# 07_EL_CON.net
KiCad netlist of a schematic drawn in Altium Designer
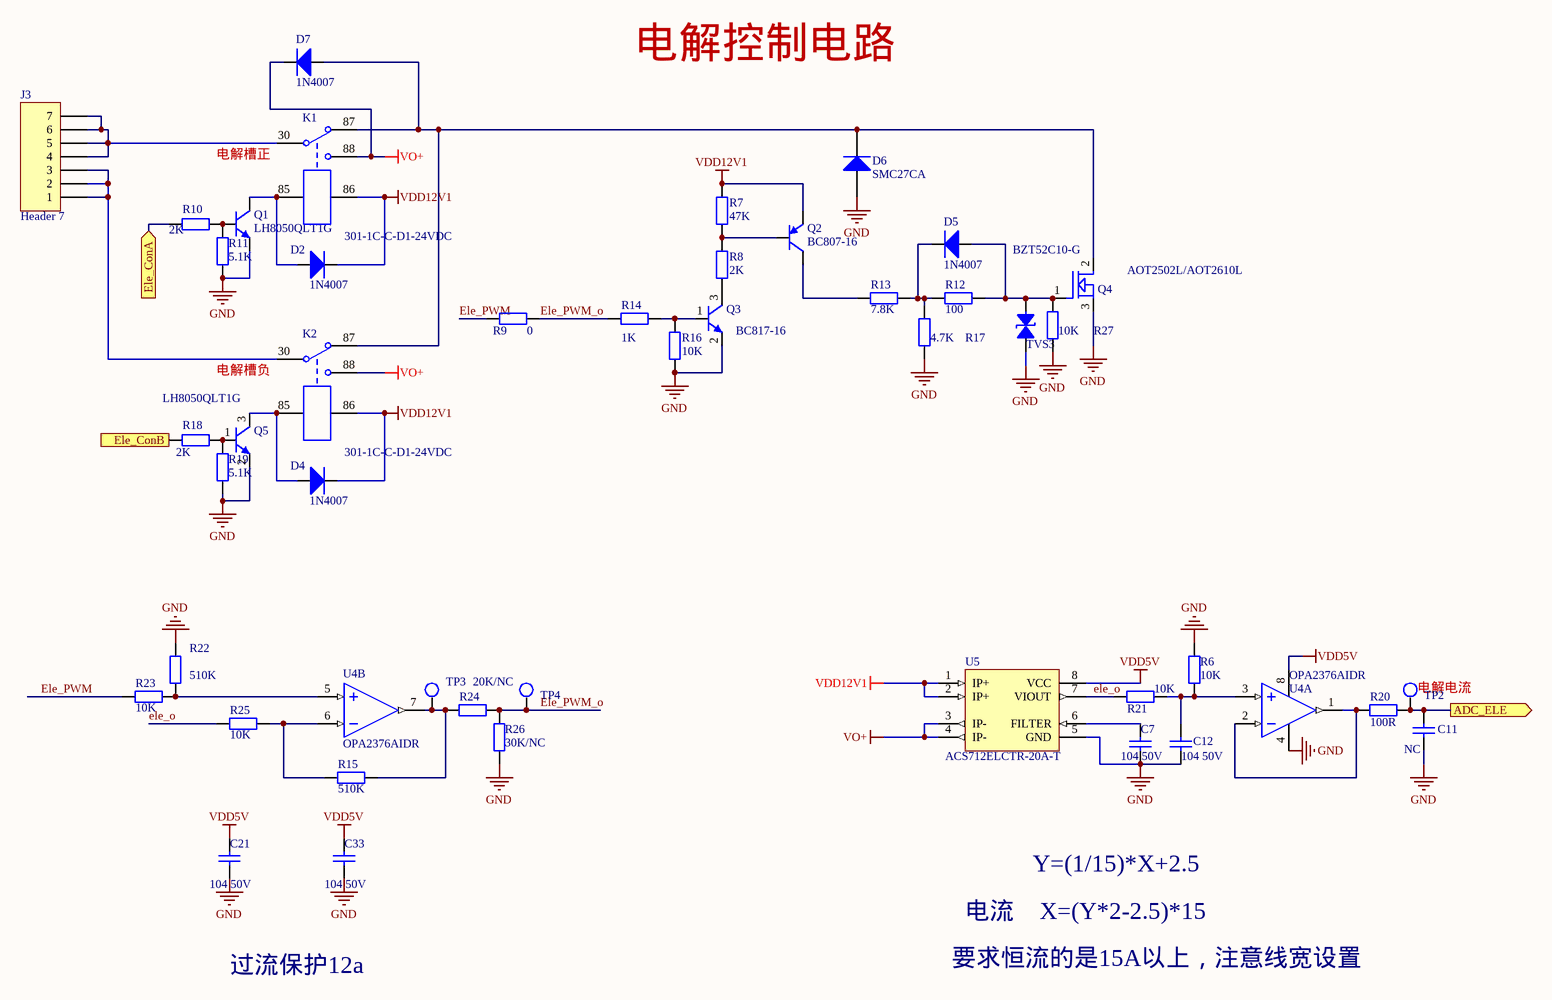
[diagram p0: 07_EL_CON.SchDoc]

(export (version "E")
  (design (tool "Eeschema 10.0.6"))
  (components
    (comp (ref "C7")
      (value "104 50V")
      (footprint "SMD-0603C")
      (description "贴片电容 10%")
      (libsource (lib "XiaoyI") (part "CAP4"))
    )
    (comp (ref "C11")
      (value "NC")
      (footprint "SMD-0603C")
      (description "贴片电容 10%")
      (libsource (lib "XiaoyI") (part "CAP4"))
    )
    (comp (ref "C12")
      (value "104 50V")
      (footprint "SMD-0603C")
      (description "贴片电容 10%")
      (libsource (lib "XiaoyI") (part "CAP4"))
    )
    (comp (ref "C21")
      (value "104 50V")
      (footprint "SMD-0603C")
      (description "贴片电容 20%")
      (libsource (lib "XiaoyI") (part "CAP4"))
    )
    (comp (ref "C33")
      (value "104 50V")
      (footprint "SMD-0603C")
      (description "贴片电容 20%")
      (libsource (lib "XiaoyI") (part "CAP4"))
    )
    (comp (ref "D2")
      (value "1N4007")
      (footprint "DO-214-AC")
      (description "贴片二极管")
      (libsource (lib "XiaoyI") (part "DIODE2"))
    )
    (comp (ref "D4")
      (value "1N4007")
      (footprint "DO-214-AC")
      (description "贴片二极管")
      (libsource (lib "XiaoyI") (part "DIODE2"))
    )
    (comp (ref "D5")
      (value "1N4007")
      (footprint "DO-214-AC")
      (description "贴片二极管")
      (libsource (lib "XiaoyI") (part "DIODE2"))
    )
    (comp (ref "D6")
      (value "SMC27CA")
      (footprint "Pcblib_20110825:SMC")
      (libsource (lib "Sch_library") (part "DIODE"))
    )
    (comp (ref "D7")
      (value "1N4007")
      (footprint "DO-214-AC")
      (description "贴片二极管")
      (libsource (lib "XiaoyI") (part "DIODE2"))
    )
    (comp (ref "J3")
      (value "Header 7")
      (footprint "VH-AW-3.96*7P")
      (description "Header, 7-Pin")
      (fields (field (name "PUBLISHER") "Altium Limited"))
      (libsource (lib "Miscellaneous Connectors") (part "Header 7"))
    )
    (comp (ref "K1")
      (value "301-1C-C-D1-24VDC")
      (footprint "PCB1:301-1C-C-R1-24VDC")
      (description "5V 继电器")
      (libsource (lib "XiaoyI") (part "JDQ1"))
    )
    (comp (ref "K2")
      (value "301-1C-C-D1-24VDC")
      (footprint "PCB1:301-1C-C-R1-24VDC")
      (description "5V 继电器")
      (libsource (lib "XiaoyI") (part "JDQ1"))
    )
    (comp (ref "Q1")
      (value "LH8050QLT1G")
      (footprint "SOT-23")
      (description "三极管")
      (libsource (lib "XiaoyI") (part "NPN-1"))
    )
    (comp (ref "Q2")
      (value "BC807-16")
      (footprint "SOT-23")
      (description "PNP")
      (libsource (lib "XiaoyI") (part "PNP"))
    )
    (comp (ref "Q3")
      (value "BC817-16")
      (footprint "SOT-23")
      (description "三极管")
      (libsource (lib "") (part "NPN-1_1"))
    )
    (comp (ref "Q4")
      (value "AOT2502L/AOT2610L")
      (footprint "Pcblib_20110825:to220")
      (libsource (lib "POWER") (part "SI7860"))
    )
    (comp (ref "Q5")
      (value "LH8050QLT1G")
      (footprint "SOT-23")
      (description "三极管")
      (libsource (lib "") (part "NPN-1_1"))
    )
    (comp (ref "R6")
      (value "10K")
      (footprint "SMD-0603")
      (description "贴片电阻 1%")
      (libsource (lib "") (part "RES0_1"))
    )
    (comp (ref "R7")
      (value "47K")
      (footprint "SMD-0603")
      (description "贴片电阻 5%")
      (libsource (lib "XiaoyI") (part "RES-SOP"))
    )
    (comp (ref "R8")
      (value "2K")
      (footprint "SMD-0603")
      (description "贴片电阻 5%")
      (libsource (lib "XiaoyI") (part "RES-SOP"))
    )
    (comp (ref "R9")
      (value "0")
      (footprint "SMD-0603")
      (description "贴片电阻 5%")
      (libsource (lib "") (part "RES-SOP_1"))
    )
    (comp (ref "R10")
      (value "2K")
      (footprint "SMD-0603")
      (description "贴片电阻 5%")
      (libsource (lib "XiaoyI") (part "RES2"))
    )
    (comp (ref "R11")
      (value "5.1K")
      (footprint "SMD-0603")
      (description "贴片电阻 5%")
      (libsource (lib "") (part "RES2_1"))
    )
    (comp (ref "R12")
      (value "100")
      (footprint "SMD-0603")
      (description "贴片电阻 5%")
      (libsource (lib "") (part "RES-SOP_3"))
    )
    (comp (ref "R13")
      (value "7.8K")
      (footprint "SMD-0603")
      (description "贴片电阻 5%")
      (libsource (lib "") (part "RES-SOP_1"))
    )
    (comp (ref "R14")
      (value "1K")
      (footprint "SMD-0603")
      (description "贴片电阻 5%")
      (libsource (lib "") (part "RES-SOP_1"))
    )
    (comp (ref "R15")
      (value "510K")
      (footprint "SMD-0603")
      (description "贴片电阻 5%")
      (libsource (lib "") (part "RES-SOP_1"))
    )
    (comp (ref "R16")
      (value "10K")
      (footprint "SMD-0603")
      (description "贴片电阻 5%")
      (libsource (lib "XiaoyI") (part "RES-SOP"))
    )
    (comp (ref "R17")
      (value "4.7K")
      (footprint "SMD-0603")
      (description "贴片电阻 5%")
      (libsource (lib "") (part "RES-SOP_2"))
    )
    (comp (ref "R18")
      (value "2K")
      (footprint "SMD-0603")
      (description "贴片电阻 5%")
      (libsource (lib "XiaoyI") (part "RES2"))
    )
    (comp (ref "R19")
      (value "5.1K")
      (footprint "SMD-0603")
      (description "贴片电阻 5%")
      (libsource (lib "") (part "RES2_1"))
    )
    (comp (ref "R20")
      (value "100R")
      (footprint "SMD-0603")
      (description "贴片电阻 5%")
      (libsource (lib "ABB") (part "RES0"))
    )
    (comp (ref "R21")
      (value "10K")
      (footprint "SMD-0603")
      (description "贴片电阻 1%")
      (libsource (lib "ABB") (part "RES0"))
    )
    (comp (ref "R22")
      (value "510K")
      (footprint "SMD-0603")
      (description "贴片电阻 5%")
      (libsource (lib "XiaoyI") (part "RES-SOP"))
    )
    (comp (ref "R23")
      (value "10K")
      (footprint "SMD-0603")
      (description "贴片电阻 5%")
      (libsource (lib "") (part "RES-SOP_1"))
    )
    (comp (ref "R24")
      (value "20K/NC")
      (footprint "SMD-0603")
      (description "贴片电阻 5%")
      (libsource (lib "") (part "RES-SOP_1"))
    )
    (comp (ref "R25")
      (value "10K")
      (footprint "SMD-0603")
      (description "贴片电阻 5%")
      (libsource (lib "") (part "RES-SOP_1"))
    )
    (comp (ref "R26")
      (value "30K/NC")
      (footprint "SMD-0603")
      (description "贴片电阻 5%")
      (libsource (lib "") (part "RES-SOP_2"))
    )
    (comp (ref "R27")
      (value "10K")
      (footprint "SMD-0603")
      (description "贴片电阻 5%")
      (libsource (lib "") (part "RES-SOP_2"))
    )
    (comp (ref "TP2") (value "TPS") (footprint "tpd") (libsource (lib "stm32") (part "TPS")))
    (comp (ref "TP3") (value "TPS") (footprint "tpd") (libsource (lib "stm32") (part "TPS")))
    (comp (ref "TP4") (value "TPS") (footprint "tpd") (libsource (lib "stm32") (part "TPS")))
    (comp (ref "TVS3")
      (value "BZT52C10-G")
      (footprint "SOD-123")
      (description "TVS 10V")
      (libsource (lib "XiaoyI") (part "TVS-1"))
    )
    (comp (ref "U4")
      (value "OPA2376AIDR")
      (footprint "SO-8")
      (description "运算放大器")
      (libsource (lib "XiaoyI") (part "LM358"))
    )
    (comp (ref "U5")
      (value "ACS712ELCTR-20A-T")
      (footprint "SO-8")
      (description "HALL 20A 电流传感器")
      (libsource (lib "XiaoyI") (part "ACS712"))
    )
  )
  (nets
    (net (code "1") (name "/ADC_ELE") (class "Default")
      (node (ref "C11") (pin "2") (pinfunction "2_2") (pintype "passive"))
      (node (ref "R20") (pin "1") (pinfunction "1_1") (pintype "passive"))
      (node (ref "TP2") (pin "1") (pinfunction "1_1") (pintype "passive"))
    )
    (net (code "2") (name "/Ele_ConA") (class "Default")
      (node (ref "R10") (pin "1") (pinfunction "1_1") (pintype "passive"))
    )
    (net (code "3") (name "/Ele_ConB") (class "Default")
      (node (ref "R18") (pin "1") (pinfunction "1_1") (pintype "passive"))
    )
    (net (code "4") (name "/Ele_PWM") (class "Default")
      (node (ref "R23") (pin "2") (pinfunction "2_2") (pintype "passive"))
      (node (ref "R9") (pin "2") (pinfunction "2_2") (pintype "passive"))
    )
    (net (code "5") (name "/Ele_PWM_o") (class "Default")
      (node (ref "R14") (pin "2") (pinfunction "2_2") (pintype "passive"))
      (node (ref "R24") (pin "1") (pinfunction "1_1") (pintype "passive"))
      (node (ref "R26") (pin "1") (pinfunction "1_1") (pintype "passive"))
      (node (ref "R9") (pin "1") (pinfunction "1_1") (pintype "passive"))
      (node (ref "TP4") (pin "1") (pinfunction "1_1") (pintype "passive"))
    )
    (net (code "6") (name "/ele_o") (class "Default")
      (node (ref "R21") (pin "2") (pinfunction "2_2") (pintype "passive"))
      (node (ref "R25") (pin "2") (pinfunction "2_2") (pintype "passive"))
      (node (ref "U5") (pin "7") (pinfunction "VIOUT_7") (pintype "output"))
    )
    (net (code "7") (name "GND") (class "Default")
      (node (ref "C11") (pin "1") (pinfunction "1_1") (pintype "passive"))
      (node (ref "C12") (pin "2") (pinfunction "2_2") (pintype "passive"))
      (node (ref "C21") (pin "1") (pinfunction "1_1") (pintype "passive"))
      (node (ref "C33") (pin "1") (pinfunction "1_1") (pintype "passive"))
      (node (ref "C7") (pin "2") (pinfunction "2_2") (pintype "passive"))
      (node (ref "D6") (pin "1") (pinfunction "A_1") (pintype "passive"))
      (node (ref "Q1") (pin "2") (pinfunction "E_2") (pintype "passive"))
      (node (ref "Q3") (pin "2") (pinfunction "E_2") (pintype "passive"))
      (node (ref "Q4") (pin "3") (pinfunction "S_3") (pintype "passive"))
      (node (ref "Q5") (pin "2") (pinfunction "E_2") (pintype "passive"))
      (node (ref "R11") (pin "1") (pinfunction "1_1") (pintype "passive"))
      (node (ref "R16") (pin "1") (pinfunction "1_1") (pintype "passive"))
      (node (ref "R17") (pin "2") (pinfunction "2_2") (pintype "passive"))
      (node (ref "R19") (pin "1") (pinfunction "1_1") (pintype "passive"))
      (node (ref "R22") (pin "2") (pinfunction "2_2") (pintype "passive"))
      (node (ref "R26") (pin "2") (pinfunction "2_2") (pintype "passive"))
      (node (ref "R27") (pin "2") (pinfunction "2_2") (pintype "passive"))
      (node (ref "R6") (pin "1") (pinfunction "1_1") (pintype "passive"))
      (node (ref "TVS3") (pin "1") (pinfunction "A_1") (pintype "passive"))
      (node (ref "U4") (pin "4") (pinfunction "V-_4") (pintype "power_in"))
      (node (ref "U5") (pin "5") (pinfunction "GND_5") (pintype "power_in"))
    )
    (net (code "8") (name "Net-(D2-A)") (class "Default")
      (node (ref "D2") (pin "1") (pinfunction "A_1") (pintype "passive"))
      (node (ref "K1") (pin "85") (pinfunction "4_85") (pintype "passive"))
      (node (ref "Q1") (pin "3") (pinfunction "C_3") (pintype "passive"))
    )
    (net (code "9") (name "Net-(D4-A)") (class "Default")
      (node (ref "D4") (pin "1") (pinfunction "A_1") (pintype "passive"))
      (node (ref "K2") (pin "85") (pinfunction "4_85") (pintype "passive"))
      (node (ref "Q5") (pin "3") (pinfunction "C_3") (pintype "passive"))
    )
    (net (code "10") (name "Net-(D5-A)") (class "Default")
      (node (ref "D5") (pin "1") (pinfunction "A_1") (pintype "passive"))
      (node (ref "Q4") (pin "1") (pinfunction "G_1") (pintype "passive"))
      (node (ref "R12") (pin "2") (pinfunction "2_2") (pintype "passive"))
      (node (ref "R27") (pin "1") (pinfunction "1_1") (pintype "passive"))
      (node (ref "TVS3") (pin "2") (pinfunction "B_2") (pintype "passive"))
    )
    (net (code "11") (name "Net-(D5-K)") (class "Default")
      (node (ref "D5") (pin "2") (pinfunction "K_2") (pintype "passive"))
      (node (ref "R12") (pin "1") (pinfunction "1_1") (pintype "passive"))
      (node (ref "R13") (pin "1") (pinfunction "1_1") (pintype "passive"))
      (node (ref "R17") (pin "1") (pinfunction "1_1") (pintype "passive"))
    )
    (net (code "12") (name "Net-(D6-K)") (class "Default")
      (node (ref "D6") (pin "2") (pinfunction "K_2") (pintype "passive"))
      (node (ref "D7") (pin "1") (pinfunction "A_1") (pintype "passive"))
      (node (ref "K1") (pin "87") (pinfunction "3_87") (pintype "passive"))
      (node (ref "K2") (pin "87") (pinfunction "3_87") (pintype "passive"))
      (node (ref "Q4") (pin "2") (pinfunction "D_2") (pintype "passive"))
    )
    (net (code "13") (name "Net-(K1-1)") (class "Default")
      (node (ref "J3") (pin "4") (pinfunction "4_4") (pintype "passive"))
      (node (ref "J3") (pin "5") (pinfunction "5_5") (pintype "passive"))
      (node (ref "J3") (pin "6") (pinfunction "6_6") (pintype "passive"))
      (node (ref "J3") (pin "7") (pinfunction "7_7") (pintype "passive"))
      (node (ref "K1") (pin "30") (pinfunction "1_30") (pintype "passive"))
    )
    (net (code "14") (name "Net-(K2-1)") (class "Default")
      (node (ref "J3") (pin "1") (pinfunction "1_1") (pintype "passive"))
      (node (ref "J3") (pin "2") (pinfunction "2_2") (pintype "passive"))
      (node (ref "J3") (pin "3") (pinfunction "3_3") (pintype "passive"))
      (node (ref "K2") (pin "30") (pinfunction "1_30") (pintype "passive"))
    )
    (net (code "15") (name "Net-(Q1-B)") (class "Default")
      (node (ref "Q1") (pin "1") (pinfunction "B_1") (pintype "passive"))
      (node (ref "R10") (pin "2") (pinfunction "2_2") (pintype "passive"))
      (node (ref "R11") (pin "2") (pinfunction "2_2") (pintype "passive"))
    )
    (net (code "16") (name "Net-(Q2-B)") (class "Default")
      (node (ref "Q2") (pin "1") (pinfunction "B_1") (pintype "passive"))
      (node (ref "R7") (pin "1") (pinfunction "1_1") (pintype "passive"))
      (node (ref "R8") (pin "2") (pinfunction "2_2") (pintype "passive"))
    )
    (net (code "17") (name "Net-(Q2-C)") (class "Default")
      (node (ref "Q2") (pin "3") (pinfunction "C_3") (pintype "passive"))
      (node (ref "R13") (pin "2") (pinfunction "2_2") (pintype "passive"))
    )
    (net (code "18") (name "Net-(Q3-B)") (class "Default")
      (node (ref "Q3") (pin "1") (pinfunction "B_1") (pintype "passive"))
      (node (ref "R14") (pin "1") (pinfunction "1_1") (pintype "passive"))
      (node (ref "R16") (pin "2") (pinfunction "2_2") (pintype "passive"))
    )
    (net (code "19") (name "Net-(Q3-C)") (class "Default")
      (node (ref "Q3") (pin "3") (pinfunction "C_3") (pintype "passive"))
      (node (ref "R8") (pin "1") (pinfunction "1_1") (pintype "passive"))
    )
    (net (code "20") (name "Net-(Q5-B)") (class "Default")
      (node (ref "Q5") (pin "1") (pinfunction "B_1") (pintype "passive"))
      (node (ref "R18") (pin "2") (pinfunction "2_2") (pintype "passive"))
      (node (ref "R19") (pin "2") (pinfunction "2_2") (pintype "passive"))
    )
    (net (code "21") (name "Net-(U4A-IN1+)") (class "Default")
      (node (ref "C12") (pin "1") (pinfunction "1_1") (pintype "passive"))
      (node (ref "R21") (pin "1") (pinfunction "1_1") (pintype "passive"))
      (node (ref "R6") (pin "2") (pinfunction "2_2") (pintype "passive"))
      (node (ref "U4") (pin "3") (pinfunction "IN1+_3") (pintype "input"))
    )
    (net (code "22") (name "Net-(U4A-IN1-)") (class "Default")
      (node (ref "R20") (pin "2") (pinfunction "2_2") (pintype "passive"))
      (node (ref "U4") (pin "1") (pinfunction "OUT1_1") (pintype "output"))
      (node (ref "U4") (pin "2") (pinfunction "IN1-_2") (pintype "input"))
    )
    (net (code "23") (name "Net-(U4B-IN2+)") (class "Default")
      (node (ref "R22") (pin "1") (pinfunction "1_1") (pintype "passive"))
      (node (ref "R23") (pin "1") (pinfunction "1_1") (pintype "passive"))
      (node (ref "U4") (pin "5") (pinfunction "IN2+_5") (pintype "input"))
    )
    (net (code "24") (name "Net-(U4B-IN2-)") (class "Default")
      (node (ref "R15") (pin "2") (pinfunction "2_2") (pintype "passive"))
      (node (ref "R25") (pin "1") (pinfunction "1_1") (pintype "passive"))
      (node (ref "U4") (pin "6") (pinfunction "IN2-_6") (pintype "input"))
    )
    (net (code "25") (name "Net-(U4B-OUT2)") (class "Default")
      (node (ref "R15") (pin "1") (pinfunction "1_1") (pintype "passive"))
      (node (ref "R24") (pin "2") (pinfunction "2_2") (pintype "passive"))
      (node (ref "TP3") (pin "1") (pinfunction "1_1") (pintype "passive"))
      (node (ref "U4") (pin "7") (pinfunction "OUT2_7") (pintype "output"))
    )
    (net (code "26") (name "Net-(U5-FILTER)") (class "Default")
      (node (ref "C7") (pin "1") (pinfunction "1_1") (pintype "passive"))
      (node (ref "U5") (pin "6") (pinfunction "FILTER_6") (pintype "input"))
    )
    (net (code "27") (name "VDD5V") (class "Default")
      (node (ref "C21") (pin "2") (pinfunction "2_2") (pintype "passive"))
      (node (ref "C33") (pin "2") (pinfunction "2_2") (pintype "passive"))
      (node (ref "U4") (pin "8") (pinfunction "V+_8") (pintype "power_in"))
      (node (ref "U5") (pin "8") (pinfunction "VCC_8") (pintype "power_in"))
    )
    (net (code "28") (name "VDD12V1") (class "Default")
      (node (ref "D2") (pin "2") (pinfunction "K_2") (pintype "passive"))
      (node (ref "D4") (pin "2") (pinfunction "K_2") (pintype "passive"))
      (node (ref "K1") (pin "86") (pinfunction "5_86") (pintype "passive"))
      (node (ref "K2") (pin "86") (pinfunction "5_86") (pintype "passive"))
      (node (ref "Q2") (pin "2") (pinfunction "E_2") (pintype "passive"))
      (node (ref "R7") (pin "2") (pinfunction "2_2") (pintype "passive"))
      (node (ref "U5") (pin "1") (pinfunction "IP+_1") (pintype "input"))
      (node (ref "U5") (pin "2") (pinfunction "IP+_2") (pintype "input"))
    )
    (net (code "29") (name "VO+") (class "Default")
      (node (ref "D7") (pin "2") (pinfunction "K_2") (pintype "passive"))
      (node (ref "K1") (pin "88") (pinfunction "2_88") (pintype "passive"))
      (node (ref "K2") (pin "88") (pinfunction "2_88") (pintype "passive"))
      (node (ref "U5") (pin "3") (pinfunction "IP-_3") (pintype "output"))
      (node (ref "U5") (pin "4") (pinfunction "IP-_4") (pintype "output"))
    )
  )
)
